# power.net
KiCad netlist of a schematic drawn in Altium Designer
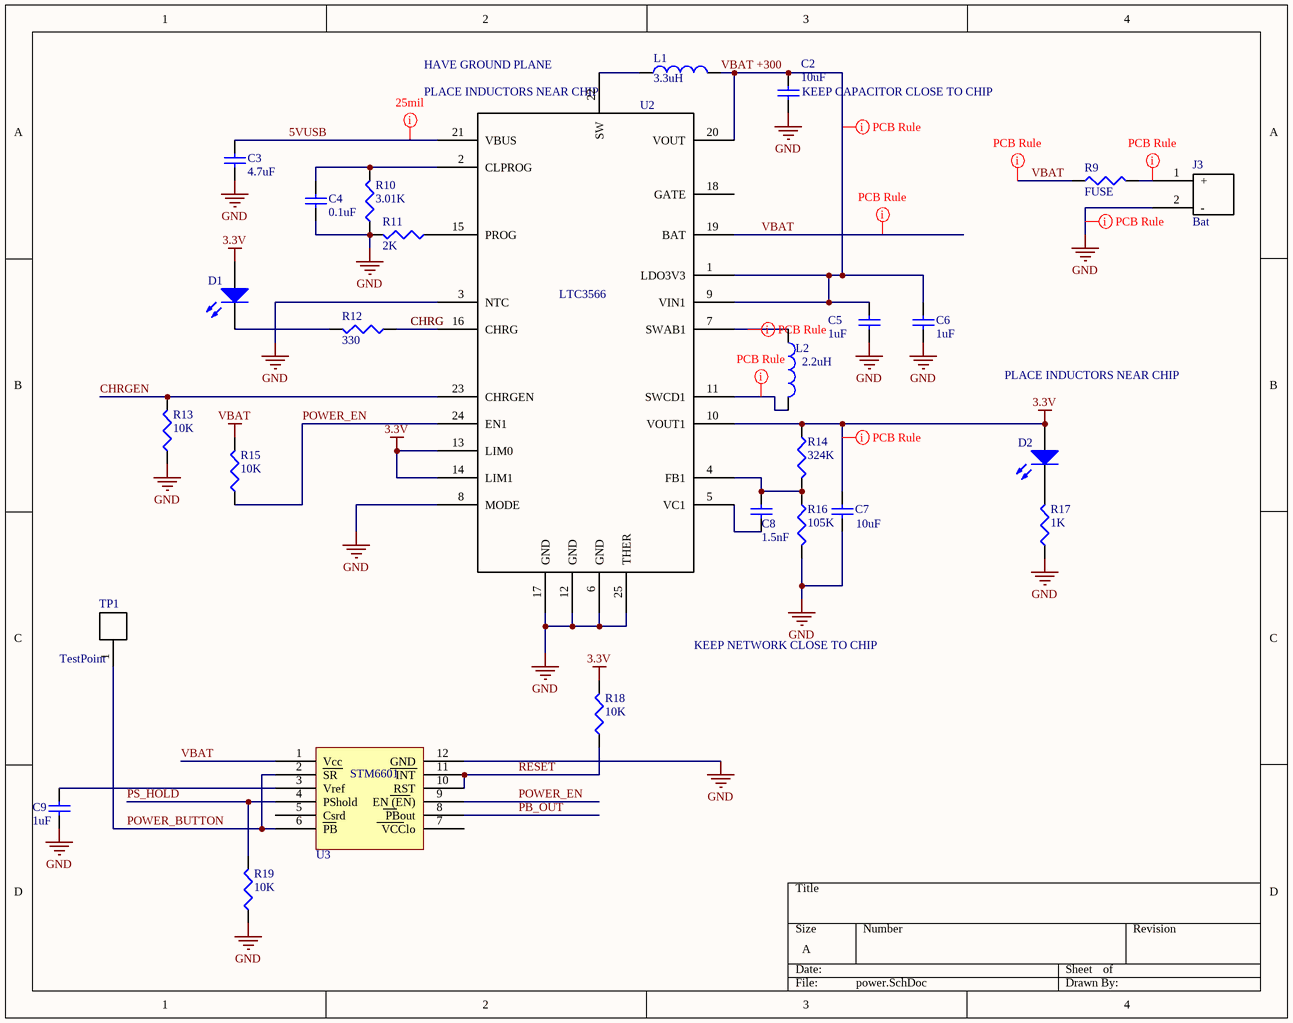
[diagram p0: power.SchDoc]

(export (version "E")
  (design (tool "Eeschema 10.0.6"))
  (components
    (comp (ref "C2")
      (value "10uF")
      (footprint "CAPC1608L")
      (description "Capacitor")
      (fields (field (name "Comment") "Cap") (field (name "PUBLISHER") "Altium Limited"))
      (libsource (lib "Miscellaneous Devices") (part "Cap"))
    )
    (comp (ref "C3")
      (value "4.7uF")
      (footprint "CAPC1608L")
      (description "Capacitor")
      (fields (field (name "Comment") "Cap") (field (name "PUBLISHER") "Altium Limited"))
      (libsource (lib "Miscellaneous Devices") (part "Cap"))
    )
    (comp (ref "C4")
      (value "0.1uF")
      (footprint "CAPC1005L")
      (description "Capacitor")
      (fields (field (name "Comment") "Cap") (field (name "PUBLISHER") "Altium Limited"))
      (libsource (lib "Miscellaneous Devices") (part "Cap"))
    )
    (comp (ref "C5")
      (value "1uF")
      (footprint "CAPC1608L")
      (description "Capacitor")
      (fields (field (name "Comment") "Cap") (field (name "PUBLISHER") "Altium Limited"))
      (libsource (lib "Miscellaneous Devices") (part "Cap"))
    )
    (comp (ref "C6")
      (value "1uF")
      (footprint "CAPC1608L")
      (description "Capacitor")
      (fields (field (name "Comment") "Cap") (field (name "PUBLISHER") "Altium Limited"))
      (libsource (lib "Miscellaneous Devices") (part "Cap"))
    )
    (comp (ref "C7")
      (value "10uF")
      (footprint "CAPC1608L")
      (description "Capacitor")
      (fields (field (name "Comment") "Cap") (field (name "PUBLISHER") "Altium Limited"))
      (libsource (lib "Miscellaneous Devices") (part "Cap"))
    )
    (comp (ref "C8")
      (value "1.5nF")
      (footprint "CAPC1005L")
      (description "Capacitor")
      (fields (field (name "Comment") "Cap") (field (name "PUBLISHER") "Altium Limited"))
      (libsource (lib "Miscellaneous Devices") (part "Cap"))
    )
    (comp (ref "C9")
      (value "1uF")
      (footprint "CAPC1608L")
      (description "Capacitor")
      (fields (field (name "Comment") "Cap") (field (name "PUBLISHER") "Altium Limited"))
      (libsource (lib "Miscellaneous Devices") (part "Cap"))
    )
    (comp (ref "D1")
      (value "Charge")
      (footprint "INDC2012L")
      (description "Typical RED, GREEN, YELLOW, AMBER GaAs LED")
      (fields (field (name "PUBLISHER") "Altium Limited"))
      (libsource (lib "Miscellaneous Devices") (part "LED2"))
    )
    (comp (ref "D2")
      (value "Power")
      (footprint "INDC2012L")
      (description "Typical RED, GREEN, YELLOW, AMBER GaAs LED")
      (fields (field (name "PUBLISHER") "Altium Limited"))
      (libsource (lib "Miscellaneous Devices") (part "LED2"))
    )
    (comp (ref "J3")
      (value "Bat")
      (footprint "BatteryConnJST")
      (libsource (lib "mrone") (part "BatteryConnJST"))
    )
    (comp (ref "L1") (value "3.3uH") (footprint "IndPow") (libsource (lib "mrone") (part "Inductor")))
    (comp (ref "L2") (value "2.2uH") (footprint "IndPow") (libsource (lib "mrone") (part "Inductor")))
    (comp (ref "R9")
      (value "FUSE")
      (footprint "RESC3225L")
      (description "Resistor")
      (fields (field (name "Comment") "Res3") (field (name "PUBLISHER") "Altium Limited"))
      (libsource (lib "Miscellaneous Devices") (part "Res3"))
    )
    (comp (ref "R10")
      (value "3.01K")
      (footprint "RESC1608L")
      (description "Resistor")
      (fields (field (name "Comment") "Res3") (field (name "PUBLISHER") "Altium Limited"))
      (libsource (lib "Miscellaneous Devices") (part "Res3"))
    )
    (comp (ref "R11")
      (value "2K")
      (footprint "RESC1608L")
      (description "Resistor")
      (fields (field (name "Comment") "Res3") (field (name "PUBLISHER") "Altium Limited"))
      (libsource (lib "Miscellaneous Devices") (part "Res3"))
    )
    (comp (ref "R12")
      (value "330")
      (footprint "RESC1608L")
      (description "Resistor")
      (fields (field (name "Comment") "Res3") (field (name "PUBLISHER") "Altium Limited"))
      (libsource (lib "Miscellaneous Devices") (part "Res3"))
    )
    (comp (ref "R13")
      (value "10K")
      (footprint "RESC1608L")
      (description "Resistor")
      (fields (field (name "Comment") "Res3") (field (name "PUBLISHER") "Altium Limited"))
      (libsource (lib "Miscellaneous Devices") (part "Res3"))
    )
    (comp (ref "R14")
      (value "324K")
      (footprint "RESC1608L")
      (description "Resistor")
      (fields (field (name "Comment") "Res3") (field (name "PUBLISHER") "Altium Limited"))
      (libsource (lib "Miscellaneous Devices") (part "Res3"))
    )
    (comp (ref "R15")
      (value "10K")
      (footprint "RESC1608L")
      (description "Resistor")
      (fields (field (name "Comment") "Res3") (field (name "PUBLISHER") "Altium Limited"))
      (libsource (lib "Miscellaneous Devices") (part "Res3"))
    )
    (comp (ref "R16")
      (value "105K")
      (footprint "RESC1608L")
      (description "Resistor")
      (fields (field (name "Comment") "Res3") (field (name "PUBLISHER") "Altium Limited"))
      (libsource (lib "Miscellaneous Devices") (part "Res3"))
    )
    (comp (ref "R17")
      (value "1K")
      (footprint "RESC1608L")
      (description "Resistor")
      (fields (field (name "Comment") "Res3") (field (name "PUBLISHER") "Altium Limited"))
      (libsource (lib "Miscellaneous Devices") (part "Res3"))
    )
    (comp (ref "R18")
      (value "10K")
      (footprint "RESC1608L")
      (description "Resistor")
      (fields (field (name "Comment") "Res3") (field (name "PUBLISHER") "Altium Limited"))
      (libsource (lib "Miscellaneous Devices") (part "Res3"))
    )
    (comp (ref "R19")
      (value "10K")
      (footprint "RESC1608L")
      (description "Resistor")
      (fields (field (name "Comment") "Res3") (field (name "PUBLISHER") "Altium Limited"))
      (libsource (lib "Miscellaneous Devices") (part "Res3"))
    )
    (comp (ref "TP1")
      (value "TestPoint")
      (footprint "TestPoint")
      (libsource (lib "mrone") (part "TestPoint"))
    )
    (comp (ref "U2")
      (value "LTC3566")
      (footprint "QFN-24")
      (libsource (lib "Schematic Components") (part "LTC3566"))
    )
    (comp (ref "U3") (value "STM6601") (footprint "TDFN12") (libsource (lib "mrone") (part "STM6601")))
  )
  (nets
    (net (code "1") (name "/5VUSB") (class "Default")
      (node (ref "C3") (pin "2") (pinfunction "2_2") (pintype "passive"))
      (node (ref "U2") (pin "21") (pinfunction "VBUS_21") (pintype "passive"))
    )
    (net (code "2") (name "/CHRG") (class "Default")
      (node (ref "R12") (pin "1") (pinfunction "1_1") (pintype "passive"))
      (node (ref "U2") (pin "16") (pinfunction "CHRG_16") (pintype "passive"))
    )
    (net (code "3") (name "/CHRGEN") (class "Default")
      (node (ref "R13") (pin "2") (pinfunction "2_2") (pintype "passive"))
      (node (ref "U2") (pin "23") (pinfunction "CHRGEN_23") (pintype "passive"))
    )
    (net (code "4") (name "/PB_OUT") (class "Default")
      (node (ref "U3") (pin "8") (pinfunction "PBout_8") (pintype "passive"))
    )
    (net (code "5") (name "/POWER_BUTTON") (class "Default")
      (node (ref "TP1") (pin "1") (pintype "passive"))
      (node (ref "U3") (pin "2") (pinfunction "SR_2") (pintype "passive"))
      (node (ref "U3") (pin "6") (pinfunction "PB_6") (pintype "passive"))
    )
    (net (code "6") (name "/POWER_EN") (class "Default")
      (node (ref "R15") (pin "1") (pinfunction "1_1") (pintype "passive"))
      (node (ref "U2") (pin "24") (pinfunction "EN1_24") (pintype "passive"))
      (node (ref "U3") (pin "9") (pinfunction "EN_(EN)_9") (pintype "passive"))
    )
    (net (code "7") (name "/PS_HOLD") (class "Default")
      (node (ref "R19") (pin "2") (pinfunction "2_2") (pintype "passive"))
      (node (ref "U3") (pin "4") (pinfunction "PShold_4") (pintype "passive"))
    )
    (net (code "8") (name "/RESET") (class "Default")
      (node (ref "R18") (pin "1") (pinfunction "1_1") (pintype "passive"))
      (node (ref "U3") (pin "10") (pinfunction "RST_10") (pintype "passive"))
      (node (ref "U3") (pin "11") (pinfunction "INT_11") (pintype "passive"))
    )
    (net (code "9") (name "/VBAT +300") (class "Default")
      (node (ref "C2") (pin "2") (pinfunction "2_2") (pintype "passive"))
      (node (ref "C5") (pin "1") (pinfunction "1_1") (pintype "passive"))
      (node (ref "C6") (pin "1") (pinfunction "1_1") (pintype "passive"))
      (node (ref "L1") (pin "2") (pinfunction "2_2") (pintype "passive"))
      (node (ref "U2") (pin "1") (pinfunction "LDO3V3_1") (pintype "passive"))
      (node (ref "U2") (pin "20") (pinfunction "VOUT_20") (pintype "passive"))
      (node (ref "U2") (pin "9") (pinfunction "VIN1_9") (pintype "passive"))
    )
    (net (code "10") (name "3.3V") (class "Default")
      (node (ref "C7") (pin "2") (pinfunction "2_2") (pintype "passive"))
      (node (ref "D1") (pin "1") (pinfunction "A_1") (pintype "passive"))
      (node (ref "D2") (pin "1") (pinfunction "A_1") (pintype "passive"))
      (node (ref "R14") (pin "1") (pinfunction "1_1") (pintype "passive"))
      (node (ref "R18") (pin "2") (pinfunction "2_2") (pintype "passive"))
      (node (ref "U2") (pin "10") (pinfunction "VOUT1_10") (pintype "passive"))
      (node (ref "U2") (pin "13") (pinfunction "LIM0_13") (pintype "passive"))
      (node (ref "U2") (pin "14") (pinfunction "LIM1_14") (pintype "passive"))
    )
    (net (code "11") (name "GND") (class "Default")
      (node (ref "C2") (pin "1") (pinfunction "1_1") (pintype "passive"))
      (node (ref "C3") (pin "1") (pinfunction "1_1") (pintype "passive"))
      (node (ref "C4") (pin "1") (pinfunction "1_1") (pintype "passive"))
      (node (ref "C5") (pin "2") (pinfunction "2_2") (pintype "passive"))
      (node (ref "C6") (pin "2") (pinfunction "2_2") (pintype "passive"))
      (node (ref "C7") (pin "1") (pinfunction "1_1") (pintype "passive"))
      (node (ref "C9") (pin "2") (pinfunction "2_2") (pintype "passive"))
      (node (ref "J3") (pin "2") (pinfunction "-_2") (pintype "passive"))
      (node (ref "R10") (pin "1") (pinfunction "1_1") (pintype "passive"))
      (node (ref "R11") (pin "2") (pinfunction "2_2") (pintype "passive"))
      (node (ref "R13") (pin "1") (pinfunction "1_1") (pintype "passive"))
      (node (ref "R16") (pin "2") (pinfunction "2_2") (pintype "passive"))
      (node (ref "R17") (pin "1") (pinfunction "1_1") (pintype "passive"))
      (node (ref "R19") (pin "1") (pinfunction "1_1") (pintype "passive"))
      (node (ref "U2") (pin "12") (pinfunction "GND_12") (pintype "passive"))
      (node (ref "U2") (pin "17") (pinfunction "GND_17") (pintype "passive"))
      (node (ref "U2") (pin "25") (pinfunction "THER_25") (pintype "passive"))
      (node (ref "U2") (pin "3") (pinfunction "NTC_3") (pintype "passive"))
      (node (ref "U2") (pin "6") (pinfunction "GND_6") (pintype "passive"))
      (node (ref "U2") (pin "8") (pinfunction "MODE_8") (pintype "passive"))
      (node (ref "U3") (pin "12") (pinfunction "GND_12") (pintype "passive"))
    )
    (net (code "12") (name "Net-(D1-K)") (class "Default")
      (node (ref "D1") (pin "2") (pinfunction "K_2") (pintype "passive"))
      (node (ref "R12") (pin "2") (pinfunction "2_2") (pintype "passive"))
    )
    (net (code "13") (name "Net-(D2-K)") (class "Default")
      (node (ref "D2") (pin "2") (pinfunction "K_2") (pintype "passive"))
      (node (ref "R17") (pin "2") (pinfunction "2_2") (pintype "passive"))
    )
    (net (code "14") (name "Net-(J3-+)") (class "Default")
      (node (ref "J3") (pin "1") (pinfunction "+_1") (pintype "passive"))
      (node (ref "R9") (pin "2") (pinfunction "2_2") (pintype "passive"))
    )
    (net (code "15") (name "Net-(U2-CLPROG)") (class "Default")
      (node (ref "C4") (pin "2") (pinfunction "2_2") (pintype "passive"))
      (node (ref "R10") (pin "2") (pinfunction "2_2") (pintype "passive"))
      (node (ref "U2") (pin "2") (pinfunction "CLPROG_2") (pintype "passive"))
    )
    (net (code "16") (name "Net-(U2-FB1)") (class "Default")
      (node (ref "C8") (pin "1") (pinfunction "1_1") (pintype "passive"))
      (node (ref "R14") (pin "2") (pinfunction "2_2") (pintype "passive"))
      (node (ref "R16") (pin "1") (pinfunction "1_1") (pintype "passive"))
      (node (ref "U2") (pin "4") (pinfunction "FB1_4") (pintype "passive"))
    )
    (net (code "17") (name "Net-(U2-PROG)") (class "Default")
      (node (ref "R11") (pin "1") (pinfunction "1_1") (pintype "passive"))
      (node (ref "U2") (pin "15") (pinfunction "PROG_15") (pintype "passive"))
    )
    (net (code "18") (name "Net-(U2-SW)") (class "Default")
      (node (ref "L1") (pin "1") (pinfunction "1_1") (pintype "passive"))
      (node (ref "U2") (pin "22") (pinfunction "SW_22") (pintype "passive"))
    )
    (net (code "19") (name "Net-(U2-SWAB1)") (class "Default")
      (node (ref "L2") (pin "1") (pinfunction "1_1") (pintype "passive"))
      (node (ref "U2") (pin "7") (pinfunction "SWAB1_7") (pintype "passive"))
    )
    (net (code "20") (name "Net-(U2-SWCD1)") (class "Default")
      (node (ref "L2") (pin "2") (pinfunction "2_2") (pintype "passive"))
      (node (ref "U2") (pin "11") (pinfunction "SWCD1_11") (pintype "passive"))
    )
    (net (code "21") (name "Net-(U2-VC1)") (class "Default")
      (node (ref "C8") (pin "2") (pinfunction "2_2") (pintype "passive"))
      (node (ref "U2") (pin "5") (pinfunction "VC1_5") (pintype "passive"))
    )
    (net (code "22") (name "Net-(U3-Vref)") (class "Default")
      (node (ref "C9") (pin "1") (pinfunction "1_1") (pintype "passive"))
      (node (ref "U3") (pin "3") (pinfunction "Vref_3") (pintype "passive"))
    )
    (net (code "23") (name "VBAT") (class "Default")
      (node (ref "R15") (pin "2") (pinfunction "2_2") (pintype "passive"))
      (node (ref "R9") (pin "1") (pinfunction "1_1") (pintype "passive"))
      (node (ref "U2") (pin "19") (pinfunction "BAT_19") (pintype "passive"))
      (node (ref "U3") (pin "1") (pinfunction "Vcc_1") (pintype "open_collector"))
    )
    (net (code "24") (name "unconnected-(U2-GATE-Pad18)") (class "Default")
      (node (ref "U2") (pin "18") (pinfunction "GATE_18") (pintype "passive"))
    )
    (net (code "25") (name "unconnected-(U3-Csrd-Pad5)") (class "Default")
      (node (ref "U3") (pin "5") (pinfunction "Csrd_5") (pintype "passive"))
    )
    (net (code "26") (name "unconnected-(U3-VCClo-Pad7)") (class "Default")
      (node (ref "U3") (pin "7") (pinfunction "VCClo_7") (pintype "passive"))
    )
  )
)
